# Power.net
KiCad netlist of a schematic drawn in Altium Designer
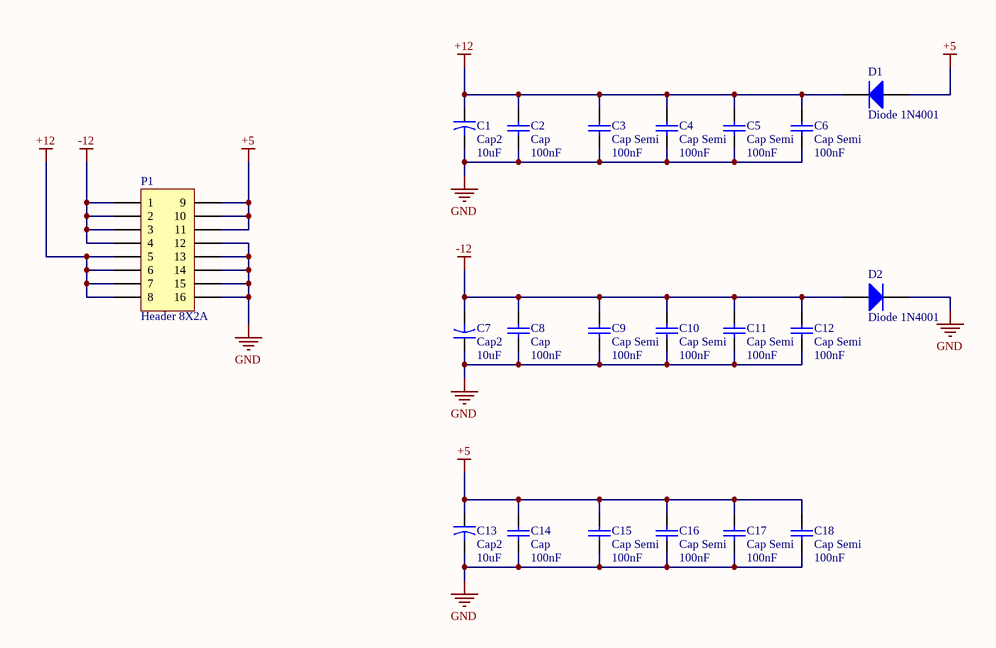
[diagram p0: Power.SchDoc]

(export (version "E")
  (design (tool "Eeschema 10.0.6"))
  (components
    (comp (ref "C1")
      (value "Cap2")
      (footprint "CAPR5-4X5")
      (description "Capacitor")
      (fields (field (name "ALTIUM_VALUE") "10uF") (field (name "PUBLISHER") "Altium Limited"))
      (libsource (lib "Miscellaneous Devices") (part "Cap2"))
    )
    (comp (ref "C2")
      (value "Cap")
      (footprint "RAD-0.3")
      (description "Capacitor")
      (fields (field (name "ALTIUM_VALUE") "100nF") (field (name "PUBLISHER") "Altium Limited"))
      (libsource (lib "Miscellaneous Devices") (part "Cap"))
    )
    (comp (ref "C3")
      (value "Cap Semi")
      (footprint "C1206")
      (description "Capacitor (Semiconductor SIM Model)")
      (fields (field (name "ALTIUM_VALUE") "100nF") (field (name "PUBLISHER") "Altium Limited"))
      (libsource (lib "Miscellaneous Devices") (part "Cap Semi"))
    )
    (comp (ref "C4")
      (value "Cap Semi")
      (footprint "C1206")
      (description "Capacitor (Semiconductor SIM Model)")
      (fields (field (name "ALTIUM_VALUE") "100nF") (field (name "PUBLISHER") "Altium Limited"))
      (libsource (lib "Miscellaneous Devices") (part "Cap Semi"))
    )
    (comp (ref "C5")
      (value "Cap Semi")
      (footprint "C1206")
      (description "Capacitor (Semiconductor SIM Model)")
      (fields (field (name "ALTIUM_VALUE") "100nF") (field (name "PUBLISHER") "Altium Limited"))
      (libsource (lib "Miscellaneous Devices") (part "Cap Semi"))
    )
    (comp (ref "C6")
      (value "Cap Semi")
      (footprint "C1206")
      (description "Capacitor (Semiconductor SIM Model)")
      (fields (field (name "ALTIUM_VALUE") "100nF") (field (name "PUBLISHER") "Altium Limited"))
      (libsource (lib "Miscellaneous Devices") (part "Cap Semi"))
    )
    (comp (ref "C7")
      (value "Cap2")
      (footprint "CAPR5-4X5")
      (description "Capacitor")
      (fields (field (name "ALTIUM_VALUE") "10uF") (field (name "PUBLISHER") "Altium Limited"))
      (libsource (lib "Miscellaneous Devices") (part "Cap2"))
    )
    (comp (ref "C8")
      (value "Cap")
      (footprint "RAD-0.3")
      (description "Capacitor")
      (fields (field (name "ALTIUM_VALUE") "100nF") (field (name "PUBLISHER") "Altium Limited"))
      (libsource (lib "Miscellaneous Devices") (part "Cap"))
    )
    (comp (ref "C9")
      (value "Cap Semi")
      (footprint "C1206")
      (description "Capacitor (Semiconductor SIM Model)")
      (fields (field (name "ALTIUM_VALUE") "100nF") (field (name "PUBLISHER") "Altium Limited"))
      (libsource (lib "Miscellaneous Devices") (part "Cap Semi"))
    )
    (comp (ref "C10")
      (value "Cap Semi")
      (footprint "C1206")
      (description "Capacitor (Semiconductor SIM Model)")
      (fields (field (name "ALTIUM_VALUE") "100nF") (field (name "PUBLISHER") "Altium Limited"))
      (libsource (lib "Miscellaneous Devices") (part "Cap Semi"))
    )
    (comp (ref "C11")
      (value "Cap Semi")
      (footprint "C1206")
      (description "Capacitor (Semiconductor SIM Model)")
      (fields (field (name "ALTIUM_VALUE") "100nF") (field (name "PUBLISHER") "Altium Limited"))
      (libsource (lib "Miscellaneous Devices") (part "Cap Semi"))
    )
    (comp (ref "C12")
      (value "Cap Semi")
      (footprint "C1206")
      (description "Capacitor (Semiconductor SIM Model)")
      (fields (field (name "ALTIUM_VALUE") "100nF") (field (name "PUBLISHER") "Altium Limited"))
      (libsource (lib "Miscellaneous Devices") (part "Cap Semi"))
    )
    (comp (ref "C13")
      (value "Cap2")
      (footprint "CAPR5-4X5")
      (description "Capacitor")
      (fields (field (name "ALTIUM_VALUE") "10uF") (field (name "PUBLISHER") "Altium Limited"))
      (libsource (lib "Miscellaneous Devices") (part "Cap2"))
    )
    (comp (ref "C14")
      (value "Cap")
      (footprint "RAD-0.3")
      (description "Capacitor")
      (fields (field (name "ALTIUM_VALUE") "100nF") (field (name "PUBLISHER") "Altium Limited"))
      (libsource (lib "Miscellaneous Devices") (part "Cap"))
    )
    (comp (ref "C15")
      (value "Cap Semi")
      (footprint "C1206")
      (description "Capacitor (Semiconductor SIM Model)")
      (fields (field (name "ALTIUM_VALUE") "100nF") (field (name "PUBLISHER") "Altium Limited"))
      (libsource (lib "Miscellaneous Devices") (part "Cap Semi"))
    )
    (comp (ref "C16")
      (value "Cap Semi")
      (footprint "C1206")
      (description "Capacitor (Semiconductor SIM Model)")
      (fields (field (name "ALTIUM_VALUE") "100nF") (field (name "PUBLISHER") "Altium Limited"))
      (libsource (lib "Miscellaneous Devices") (part "Cap Semi"))
    )
    (comp (ref "C17")
      (value "Cap Semi")
      (footprint "C1206")
      (description "Capacitor (Semiconductor SIM Model)")
      (fields (field (name "ALTIUM_VALUE") "100nF") (field (name "PUBLISHER") "Altium Limited"))
      (libsource (lib "Miscellaneous Devices") (part "Cap Semi"))
    )
    (comp (ref "C18")
      (value "Cap Semi")
      (footprint "C1206")
      (description "Capacitor (Semiconductor SIM Model)")
      (fields (field (name "ALTIUM_VALUE") "100nF") (field (name "PUBLISHER") "Altium Limited"))
      (libsource (lib "Miscellaneous Devices") (part "Cap Semi"))
    )
    (comp (ref "D1")
      (value "Diode 1N4001")
      (footprint "DO-41")
      (description "1 Amp General Purpose Rectifier")
      (fields (field (name "PUBLISHER") "Altium Limited"))
      (libsource (lib "Miscellaneous Devices") (part "Diode 1N4001"))
    )
    (comp (ref "D2")
      (value "Diode 1N4001")
      (footprint "DO-41")
      (description "1 Amp General Purpose Rectifier")
      (fields (field (name "PUBLISHER") "Altium Limited"))
      (libsource (lib "Miscellaneous Devices") (part "Diode 1N4001"))
    )
    (comp (ref "P1")
      (value "Header 8X2A")
      (footprint "HDR2X8_CEN")
      (description "Header, 8-Pin, Dual row")
      (fields (field (name "PUBLISHER") "Altium Limited"))
      (libsource (lib "Miscellaneous Connectors") (part "Header 8X2A"))
    )
  )
  (nets
    (net (code "1") (name "+5") (class "Default")
      (node (ref "C13") (pin "1") (pinfunction "1_1") (pintype "passive"))
      (node (ref "C14") (pin "2") (pinfunction "2_2") (pintype "passive"))
      (node (ref "C15") (pin "1") (pinfunction "1_1") (pintype "passive"))
      (node (ref "C16") (pin "1") (pinfunction "1_1") (pintype "passive"))
      (node (ref "C17") (pin "1") (pinfunction "1_1") (pintype "passive"))
      (node (ref "C18") (pin "1") (pinfunction "1_1") (pintype "passive"))
      (node (ref "D1") (pin "1") (pinfunction "A_1") (pintype "passive"))
      (node (ref "P1") (pin "10") (pinfunction "10_10") (pintype "passive"))
      (node (ref "P1") (pin "11") (pinfunction "11_11") (pintype "passive"))
      (node (ref "P1") (pin "9") (pinfunction "9_9") (pintype "passive"))
    )
    (net (code "2") (name "+12") (class "Default")
      (node (ref "C1") (pin "1") (pinfunction "1_1") (pintype "passive"))
      (node (ref "C2") (pin "2") (pinfunction "2_2") (pintype "passive"))
      (node (ref "C3") (pin "1") (pinfunction "1_1") (pintype "passive"))
      (node (ref "C4") (pin "1") (pinfunction "1_1") (pintype "passive"))
      (node (ref "C5") (pin "1") (pinfunction "1_1") (pintype "passive"))
      (node (ref "C6") (pin "1") (pinfunction "1_1") (pintype "passive"))
      (node (ref "D1") (pin "2") (pinfunction "K_2") (pintype "passive"))
      (node (ref "P1") (pin "5") (pinfunction "5_5") (pintype "passive"))
      (node (ref "P1") (pin "6") (pinfunction "6_6") (pintype "passive"))
      (node (ref "P1") (pin "7") (pinfunction "7_7") (pintype "passive"))
      (node (ref "P1") (pin "8") (pinfunction "8_8") (pintype "passive"))
    )
    (net (code "3") (name "-12") (class "Default")
      (node (ref "C10") (pin "1") (pinfunction "1_1") (pintype "passive"))
      (node (ref "C11") (pin "1") (pinfunction "1_1") (pintype "passive"))
      (node (ref "C12") (pin "1") (pinfunction "1_1") (pintype "passive"))
      (node (ref "C7") (pin "2") (pinfunction "2_2") (pintype "passive"))
      (node (ref "C8") (pin "2") (pinfunction "2_2") (pintype "passive"))
      (node (ref "C9") (pin "1") (pinfunction "1_1") (pintype "passive"))
      (node (ref "D2") (pin "1") (pinfunction "A_1") (pintype "passive"))
      (node (ref "P1") (pin "1") (pinfunction "1_1") (pintype "passive"))
      (node (ref "P1") (pin "2") (pinfunction "2_2") (pintype "passive"))
      (node (ref "P1") (pin "3") (pinfunction "3_3") (pintype "passive"))
      (node (ref "P1") (pin "4") (pinfunction "4_4") (pintype "passive"))
    )
    (net (code "4") (name "GND") (class "Default")
      (node (ref "C1") (pin "2") (pinfunction "2_2") (pintype "passive"))
      (node (ref "C10") (pin "2") (pinfunction "2_2") (pintype "passive"))
      (node (ref "C11") (pin "2") (pinfunction "2_2") (pintype "passive"))
      (node (ref "C12") (pin "2") (pinfunction "2_2") (pintype "passive"))
      (node (ref "C13") (pin "2") (pinfunction "2_2") (pintype "passive"))
      (node (ref "C14") (pin "1") (pinfunction "1_1") (pintype "passive"))
      (node (ref "C15") (pin "2") (pinfunction "2_2") (pintype "passive"))
      (node (ref "C16") (pin "2") (pinfunction "2_2") (pintype "passive"))
      (node (ref "C17") (pin "2") (pinfunction "2_2") (pintype "passive"))
      (node (ref "C18") (pin "2") (pinfunction "2_2") (pintype "passive"))
      (node (ref "C2") (pin "1") (pinfunction "1_1") (pintype "passive"))
      (node (ref "C3") (pin "2") (pinfunction "2_2") (pintype "passive"))
      (node (ref "C4") (pin "2") (pinfunction "2_2") (pintype "passive"))
      (node (ref "C5") (pin "2") (pinfunction "2_2") (pintype "passive"))
      (node (ref "C6") (pin "2") (pinfunction "2_2") (pintype "passive"))
      (node (ref "C7") (pin "1") (pinfunction "1_1") (pintype "passive"))
      (node (ref "C8") (pin "1") (pinfunction "1_1") (pintype "passive"))
      (node (ref "C9") (pin "2") (pinfunction "2_2") (pintype "passive"))
      (node (ref "D2") (pin "2") (pinfunction "K_2") (pintype "passive"))
      (node (ref "P1") (pin "12") (pinfunction "12_12") (pintype "passive"))
      (node (ref "P1") (pin "13") (pinfunction "13_13") (pintype "passive"))
      (node (ref "P1") (pin "14") (pinfunction "14_14") (pintype "passive"))
      (node (ref "P1") (pin "15") (pinfunction "15_15") (pintype "passive"))
      (node (ref "P1") (pin "16") (pinfunction "16_16") (pintype "passive"))
    )
  )
)
